# schematic.net
KiCad netlist of a schematic drawn in EasyEDA
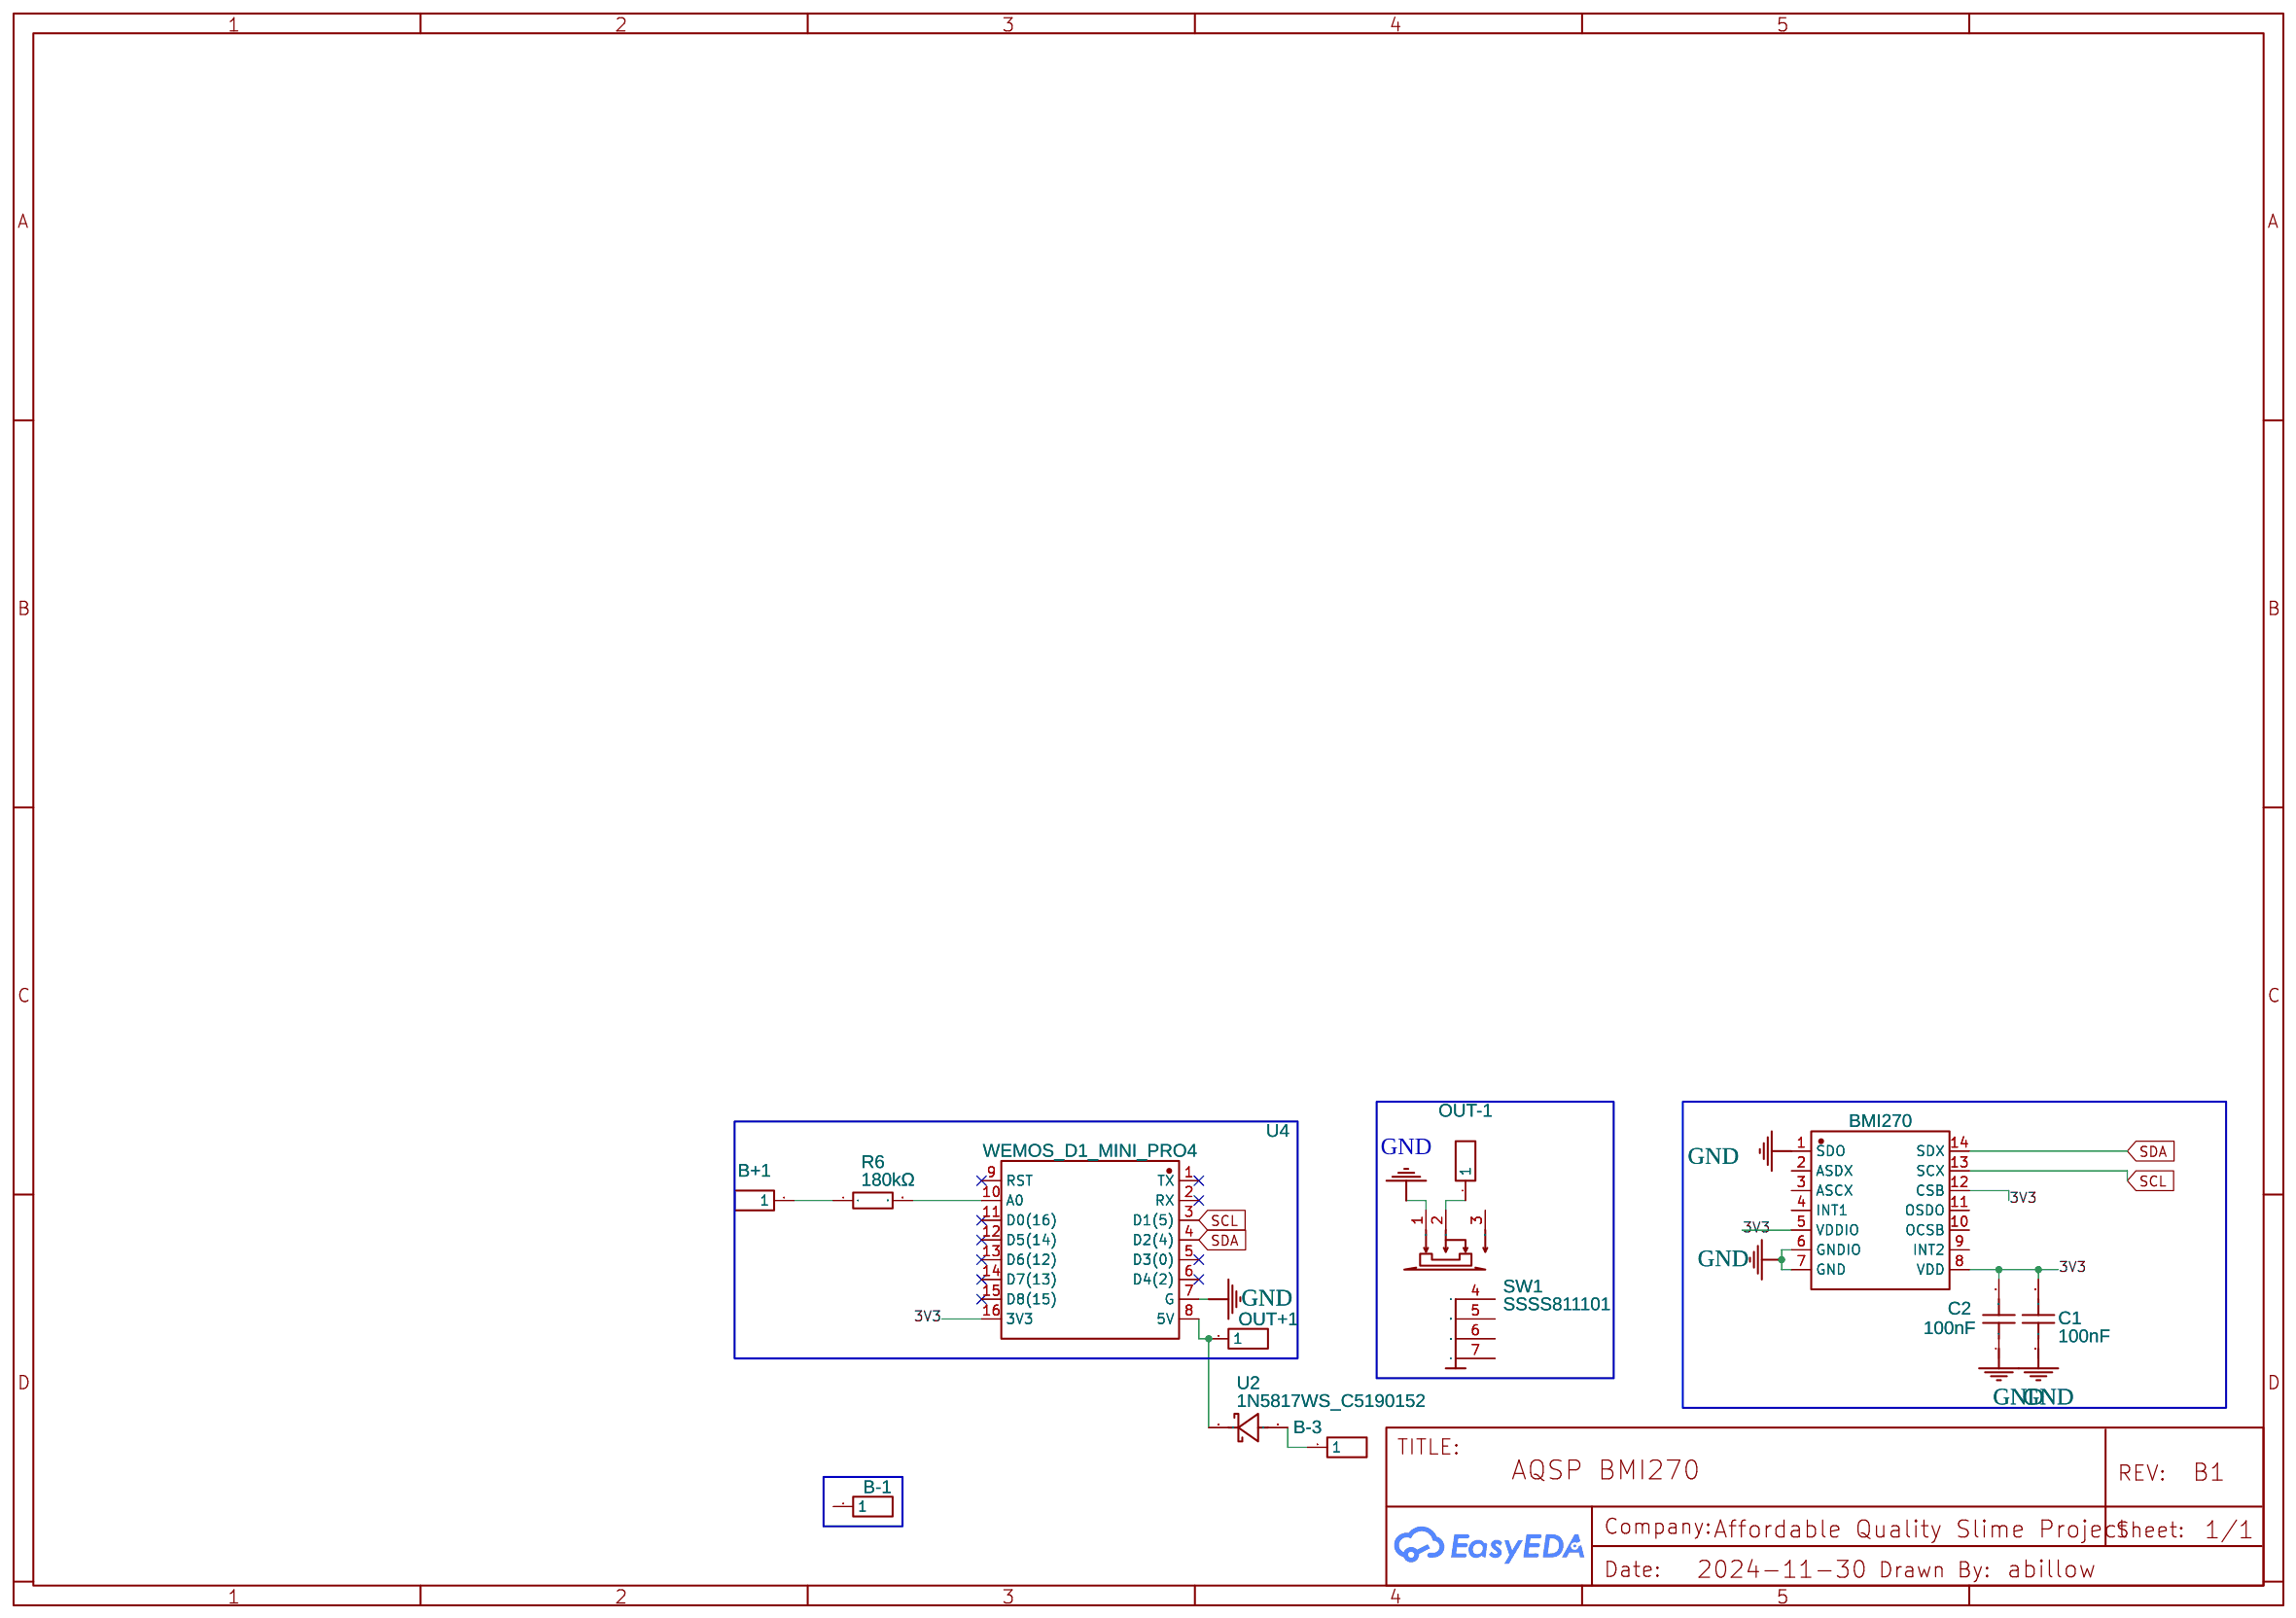
[diagram p0: schematic sheet]

(export (version "E")
  (design (tool "Eeschema 10.0.6"))
  (components
    (comp (ref "B+1")
      (value "Header-Male-2.54_1x1")
      (fields (field (name "Manufacturer") "ReliaPro"))
      (libsource (lib "") (part "Unknown_380_-205"))
    )
    (comp (ref "B-1")
      (value "Header-Male-2.54_1x1")
      (fields (field (name "Manufacturer") "ReliaPro"))
      (libsource (lib "") (part "Unknown_430_-50"))
    )
    (comp (ref "B-3")
      (value "Header-Male-2.54_1x1")
      (fields (field (name "Manufacturer") "ReliaPro"))
      (libsource (lib "") (part "Unknown_670_-80"))
    )
    (comp (ref "C1")
      (value "100nF")
      (fields (field (name "Manufacturer Part") "FN15X104K500PKG") (field (name "Manufacturer") "PSA(信昌电陶)"))
      (libsource (lib "") (part "FN15X104K500PKG"))
    )
    (comp (ref "C2")
      (value "100nF")
      (fields (field (name "Manufacturer Part") "FN15X104K500PKG") (field (name "Manufacturer") "PSA(信昌电陶)"))
      (libsource (lib "") (part "FN15X104K500PKG"))
    )
    (comp (ref "OUT+1")
      (value "Header-Male-2.54_1x1")
      (fields (field (name "Manufacturer") "ReliaPro"))
      (libsource (lib "") (part "Unknown_620_-135"))
    )
    (comp (ref "OUT-1")
      (value "Header-Male-2.54_1x1")
      (fields (field (name "Manufacturer") "ReliaPro"))
      (libsource (lib "") (part "Unknown_735_-220"))
    )
    (comp (ref "R6")
      (value "180kΩ")
      (fields
        (field (name "Manufacturer Part") "MF1/4W-180KΩ±1% T")
        (field (name "Manufacturer") "CCO(千志电子)")
      )
      (libsource (lib "") (part "MF1/4W-180KΩ±1% T52"))
    )
    (comp (ref "SW1")
      (value "SSSS811101")
      (fields (field (name "Manufacturer") "ALPSALPINE(阿尔卑斯阿尔派)"))
      (libsource (lib "") (part "SSSS811101"))
    )
    (comp (ref "U1")
      (value "BMI270")
      (fields (field (name "Manufacturer") "Bosch(博世)"))
      (libsource (lib "") (part "BMI270"))
    )
    (comp (ref "U2")
      (value "1N5817WS_C5190152")
      (fields (field (name "Manufacturer Part") "1N5817WS") (field (name "Manufacturer") "Hottech(合科泰)"))
      (libsource (lib "") (part "1N5817WS_C5190152"))
    )
    (comp (ref "U4")
      (value "WEMOS_D1_MINI_PRO4")
      (fields (field (name "Manufacturer Part") "Wemos_D1_mini_Pro4"))
      (libsource (lib "") (part "WEMOS_D1_MINI_PRO4"))
    )
  )
  (nets
    (net (code "1") (name "/3V3") (class "Default")
      (node (ref "C1") (pin "2") (pinfunction "2_2") (pintype "unspecified"))
      (node (ref "C2") (pin "2") (pinfunction "2_2") (pintype "unspecified"))
      (node (ref "U1") (pin "12") (pinfunction "CSB_12") (pintype "unspecified"))
      (node (ref "U1") (pin "5") (pinfunction "VDDIO_5") (pintype "unspecified"))
      (node (ref "U1") (pin "8") (pinfunction "VDD_8") (pintype "unspecified"))
      (node (ref "U4") (pin "16") (pinfunction "3V3_16") (pintype "unspecified"))
    )
    (net (code "2") (name "GND") (class "Default")
      (node (ref "C1") (pin "1") (pinfunction "1_1") (pintype "unspecified"))
      (node (ref "C2") (pin "1") (pinfunction "1_1") (pintype "unspecified"))
      (node (ref "SW1") (pin "1") (pinfunction "1_1") (pintype "unspecified"))
      (node (ref "U1") (pin "1") (pinfunction "SDO_1") (pintype "unspecified"))
      (node (ref "U1") (pin "6") (pinfunction "GNDIO_6") (pintype "unspecified"))
      (node (ref "U1") (pin "7") (pinfunction "GND_7") (pintype "unspecified"))
      (node (ref "U4") (pin "7") (pinfunction "G_7") (pintype "unspecified"))
    )
    (net (code "3") (name "Net-(B+1-Pad1)") (class "Default")
      (node (ref "B+1") (pin "1") (pinfunction "1_1") (pintype "input"))
      (node (ref "R6") (pin "1") (pinfunction "1_1") (pintype "unspecified"))
    )
    (net (code "4") (name "Net-(OUT-1-Pad1)") (class "Default")
      (node (ref "OUT-1") (pin "1") (pinfunction "1_1") (pintype "input"))
      (node (ref "SW1") (pin "2") (pinfunction "2_2") (pintype "unspecified"))
    )
    (net (code "5") (name "Net-(U2-A)") (class "Default")
      (node (ref "B-3") (pin "1") (pinfunction "1_1") (pintype "input"))
      (node (ref "U2") (pin "2") (pinfunction "A_2") (pintype "unspecified"))
    )
    (net (code "6") (name "Net-(U2-C)") (class "Default")
      (node (ref "OUT+1") (pin "1") (pinfunction "1_1") (pintype "input"))
      (node (ref "U2") (pin "1") (pinfunction "C_1") (pintype "unspecified"))
      (node (ref "U4") (pin "8") (pinfunction "5V_8") (pintype "unspecified"))
    )
    (net (code "7") (name "Net-(U4-A0)") (class "Default")
      (node (ref "R6") (pin "2") (pinfunction "2_2") (pintype "unspecified"))
      (node (ref "U4") (pin "10") (pinfunction "A0_10") (pintype "unspecified"))
    )
    (net (code "8") (name "SCL") (class "Default")
      (node (ref "U1") (pin "13") (pinfunction "SCX_13") (pintype "unspecified"))
      (node (ref "U4") (pin "3") (pinfunction "D1(5)_3") (pintype "unspecified"))
    )
    (net (code "9") (name "SDA") (class "Default")
      (node (ref "U1") (pin "14") (pinfunction "SDX_14") (pintype "unspecified"))
      (node (ref "U4") (pin "4") (pinfunction "D2(4)_4") (pintype "unspecified"))
    )
    (net (code "10") (name "unconnected-(B-1-Pad1)") (class "Default")
      (node (ref "B-1") (pin "1") (pinfunction "1_1") (pintype "input"))
    )
    (net (code "11") (name "unconnected-(SW1-Pad3)") (class "Default")
      (node (ref "SW1") (pin "3") (pinfunction "3_3") (pintype "unspecified"))
    )
    (net (code "12") (name "unconnected-(SW1-Pad4)") (class "Default")
      (node (ref "SW1") (pin "4") (pinfunction "4_4") (pintype "unspecified"))
    )
    (net (code "13") (name "unconnected-(SW1-Pad5)") (class "Default")
      (node (ref "SW1") (pin "5") (pinfunction "5_5") (pintype "unspecified"))
    )
    (net (code "14") (name "unconnected-(SW1-Pad6)") (class "Default")
      (node (ref "SW1") (pin "6") (pinfunction "6_6") (pintype "unspecified"))
    )
    (net (code "15") (name "unconnected-(SW1-Pad7)") (class "Default")
      (node (ref "SW1") (pin "7") (pinfunction "7_7") (pintype "unspecified"))
    )
    (net (code "16") (name "unconnected-(U1-ASCX-Pad3)") (class "Default")
      (node (ref "U1") (pin "3") (pinfunction "ASCX_3") (pintype "unspecified"))
    )
    (net (code "17") (name "unconnected-(U1-ASDX-Pad2)") (class "Default")
      (node (ref "U1") (pin "2") (pinfunction "ASDX_2") (pintype "unspecified"))
    )
    (net (code "18") (name "unconnected-(U1-INT1-Pad4)") (class "Default")
      (node (ref "U1") (pin "4") (pinfunction "INT1_4") (pintype "unspecified"))
    )
    (net (code "19") (name "unconnected-(U1-INT2-Pad9)") (class "Default")
      (node (ref "U1") (pin "9") (pinfunction "INT2_9") (pintype "unspecified"))
    )
    (net (code "20") (name "unconnected-(U1-OCSB-Pad10)") (class "Default")
      (node (ref "U1") (pin "10") (pinfunction "OCSB_10") (pintype "unspecified"))
    )
    (net (code "21") (name "unconnected-(U1-OSDO-Pad11)") (class "Default")
      (node (ref "U1") (pin "11") (pinfunction "OSDO_11") (pintype "unspecified"))
    )
    (net (code "22") (name "unconnected-(U4-D0(16)-Pad11)") (class "Default")
      (node (ref "U4") (pin "11") (pinfunction "D0(16)_11") (pintype "unspecified+no_connect"))
    )
    (net (code "23") (name "unconnected-(U4-D3(0)-Pad5)") (class "Default")
      (node (ref "U4") (pin "5") (pinfunction "D3(0)_5") (pintype "unspecified+no_connect"))
    )
    (net (code "24") (name "unconnected-(U4-D4(2)-Pad6)") (class "Default")
      (node (ref "U4") (pin "6") (pinfunction "D4(2)_6") (pintype "unspecified+no_connect"))
    )
    (net (code "25") (name "unconnected-(U4-D5(14)-Pad12)") (class "Default")
      (node (ref "U4") (pin "12") (pinfunction "D5(14)_12") (pintype "unspecified+no_connect"))
    )
    (net (code "26") (name "unconnected-(U4-D6(12)-Pad13)") (class "Default")
      (node (ref "U4") (pin "13") (pinfunction "D6(12)_13") (pintype "unspecified+no_connect"))
    )
    (net (code "27") (name "unconnected-(U4-D7(13)-Pad14)") (class "Default")
      (node (ref "U4") (pin "14") (pinfunction "D7(13)_14") (pintype "unspecified+no_connect"))
    )
    (net (code "28") (name "unconnected-(U4-D8(15)-Pad15)") (class "Default")
      (node (ref "U4") (pin "15") (pinfunction "D8(15)_15") (pintype "unspecified+no_connect"))
    )
    (net (code "29") (name "unconnected-(U4-RST-Pad9)") (class "Default")
      (node (ref "U4") (pin "9") (pinfunction "RST_9") (pintype "unspecified+no_connect"))
    )
    (net (code "30") (name "unconnected-(U4-RX-Pad2)") (class "Default")
      (node (ref "U4") (pin "2") (pinfunction "RX_2") (pintype "unspecified+no_connect"))
    )
    (net (code "31") (name "unconnected-(U4-TX-Pad1)") (class "Default")
      (node (ref "U4") (pin "1") (pinfunction "TX_1") (pintype "unspecified+no_connect"))
    )
  )
)
